# Schema.net
KiCad netlist of a schematic drawn in Altium Designer
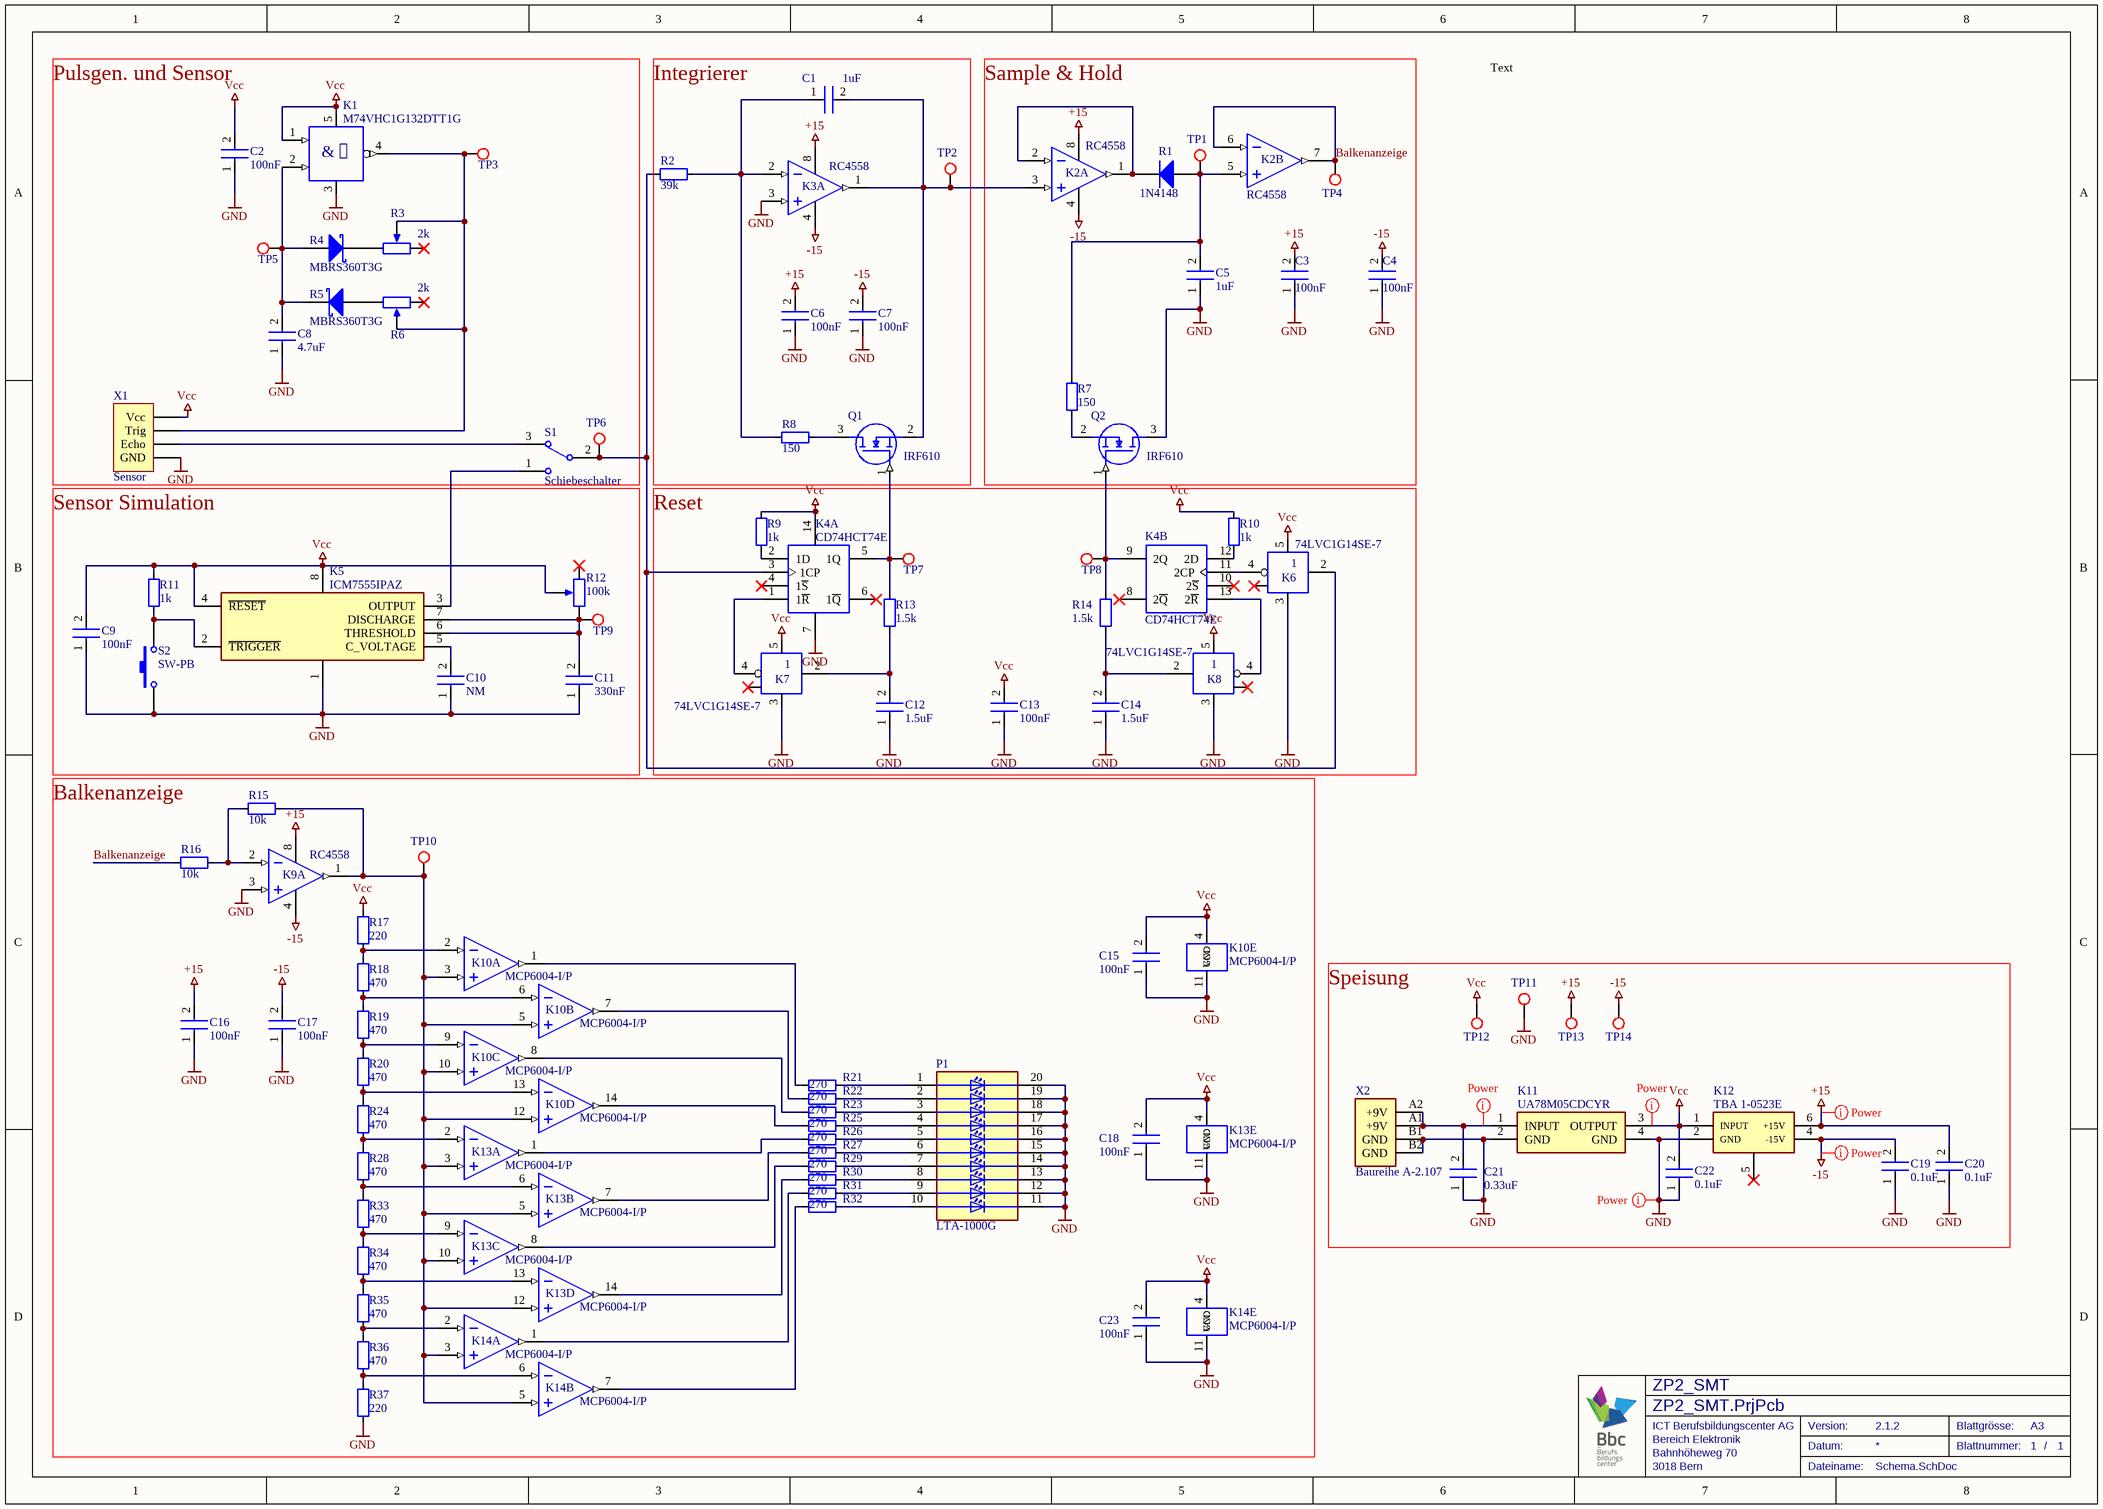
[diagram p0: Schema.SchDoc]

(export (version "E")
  (design (tool "Eeschema 10.0.6"))
  (components
    (comp (ref "C1")
      (value "1uF")
      (footprint "Footprints:okCAP CER 1206 H")
      (description "Capacitor")
      (fields
        (field (name "MANUFACTURER_PART_NUMBER") "08055A101JAT2A")
        (field (name "MOUSER PART NUMBER") "581-08055A101J")
      )
      (libsource (lib "SchemaLibrary") (part "CAP0805"))
    )
    (comp (ref "C2")
      (value "100nF")
      (footprint "Footprints:okCAP CER 1206 H")
      (description "Capacitor")
      (fields
        (field (name "MANUFACTURER_PART_NUMBER") "08055A101JAT2A")
        (field (name "MOUSER PART NUMBER") "581-08055A101J")
      )
      (libsource (lib "SchemaLibrary") (part "CAP0805"))
    )
    (comp (ref "C3")
      (value "100nF")
      (footprint "Footprints:okCAP CER 1206 H")
      (description "Capacitor")
      (fields
        (field (name "MANUFACTURER_PART_NUMBER") "08055A101JAT2A")
        (field (name "MOUSER PART NUMBER") "581-08055A101J")
      )
      (libsource (lib "SchemaLibrary") (part "CAP0805"))
    )
    (comp (ref "C4")
      (value "100nF")
      (footprint "Footprints:okCAP CER 1206 H")
      (description "Capacitor")
      (fields
        (field (name "MANUFACTURER_PART_NUMBER") "08055A101JAT2A")
        (field (name "MOUSER PART NUMBER") "581-08055A101J")
      )
      (libsource (lib "SchemaLibrary") (part "CAP0805"))
    )
    (comp (ref "C5")
      (value "1uF")
      (footprint "Footprints:okCAP CER 1206 H")
      (description "Capacitor")
      (fields
        (field (name "MANUFACTURER_PART_NUMBER") "08055A101JAT2A")
        (field (name "MOUSER PART NUMBER") "581-08055A101J")
      )
      (libsource (lib "SchemaLibrary") (part "CAP0805"))
    )
    (comp (ref "C6")
      (value "100nF")
      (footprint "Footprints:okCAP CER 1206 H")
      (description "Capacitor")
      (fields
        (field (name "MANUFACTURER_PART_NUMBER") "08055A101JAT2A")
        (field (name "MOUSER PART NUMBER") "581-08055A101J")
      )
      (libsource (lib "SchemaLibrary") (part "CAP0805"))
    )
    (comp (ref "C7")
      (value "100nF")
      (footprint "Footprints:okCAP CER 1206 H")
      (description "Capacitor")
      (fields
        (field (name "MANUFACTURER_PART_NUMBER") "08055A101JAT2A")
        (field (name "MOUSER PART NUMBER") "581-08055A101J")
      )
      (libsource (lib "SchemaLibrary") (part "CAP0805"))
    )
    (comp (ref "C8")
      (value "4.7uF")
      (footprint "Footprints:okCAP CER 1206 H")
      (description "Capacitor")
      (fields
        (field (name "MANUFACTURER_PART_NUMBER") "08055A101JAT2A")
        (field (name "MOUSER PART NUMBER") "581-08055A101J")
      )
      (libsource (lib "SchemaLibrary") (part "CAP0805"))
    )
    (comp (ref "C9")
      (value "100nF")
      (footprint "Footprints:okCAP CER 1206 H")
      (description "Capacitor")
      (fields
        (field (name "MANUFACTURER_PART_NUMBER") "08055A101JAT2A")
        (field (name "MOUSER PART NUMBER") "581-08055A101J")
      )
      (libsource (lib "SchemaLibrary") (part "CAP0805"))
    )
    (comp (ref "C10")
      (value "NM")
      (footprint "Footprints:okCAP CER 1206 H")
      (description "Capacitor")
      (fields
        (field (name "MANUFACTURER_PART_NUMBER") "08055A101JAT2A")
        (field (name "MOUSER PART NUMBER") "581-08055A101J")
      )
      (libsource (lib "SchemaLibrary") (part "CAP0805"))
    )
    (comp (ref "C11")
      (value "330nF")
      (footprint "Footprints:okCAP CER 1206 H")
      (description "Capacitor")
      (fields
        (field (name "MANUFACTURER_PART_NUMBER") "08055A101JAT2A")
        (field (name "MOUSER PART NUMBER") "581-08055A101J")
      )
      (libsource (lib "SchemaLibrary") (part "CAP0805"))
    )
    (comp (ref "C12")
      (value "1.5uF")
      (footprint "Footprints:okCAP CER 1206 H")
      (description "Capacitor")
      (fields
        (field (name "MANUFACTURER_PART_NUMBER") "08055A101JAT2A")
        (field (name "MOUSER PART NUMBER") "581-08055A101J")
      )
      (libsource (lib "SchemaLibrary") (part "CAP0805"))
    )
    (comp (ref "C13")
      (value "100nF")
      (footprint "Footprints:okCAP CER 1206 H")
      (description "Capacitor")
      (fields
        (field (name "MANUFACTURER_PART_NUMBER") "08055A101JAT2A")
        (field (name "MOUSER PART NUMBER") "581-08055A101J")
      )
      (libsource (lib "SchemaLibrary") (part "CAP0805"))
    )
    (comp (ref "C14")
      (value "1.5uF")
      (footprint "Footprints:okCAP CER 1206 H")
      (description "Capacitor")
      (fields
        (field (name "MANUFACTURER_PART_NUMBER") "08055A101JAT2A")
        (field (name "MOUSER PART NUMBER") "581-08055A101J")
      )
      (libsource (lib "SchemaLibrary") (part "CAP0805"))
    )
    (comp (ref "C15")
      (value "100nF")
      (footprint "Footprints:okCAP CER 1206 H")
      (description "Capacitor")
      (fields
        (field (name "MANUFACTURER_PART_NUMBER") "08055A101JAT2A")
        (field (name "MOUSER PART NUMBER") "581-08055A101J")
      )
      (libsource (lib "SchemaLibrary") (part "CAP0805"))
    )
    (comp (ref "C16")
      (value "100nF")
      (footprint "Footprints:okCAP CER 1206 H")
      (description "Capacitor")
      (fields
        (field (name "MANUFACTURER_PART_NUMBER") "08055A101JAT2A")
        (field (name "MOUSER PART NUMBER") "581-08055A101J")
      )
      (libsource (lib "SchemaLibrary") (part "CAP0805"))
    )
    (comp (ref "C17")
      (value "100nF")
      (footprint "Footprints:okCAP CER 1206 H")
      (description "Capacitor")
      (fields
        (field (name "MANUFACTURER_PART_NUMBER") "08055A101JAT2A")
        (field (name "MOUSER PART NUMBER") "581-08055A101J")
      )
      (libsource (lib "SchemaLibrary") (part "CAP0805"))
    )
    (comp (ref "C18")
      (value "100nF")
      (footprint "Footprints:okCAP CER 1206 H")
      (description "Capacitor")
      (fields
        (field (name "MANUFACTURER_PART_NUMBER") "08055A101JAT2A")
        (field (name "MOUSER PART NUMBER") "581-08055A101J")
      )
      (libsource (lib "SchemaLibrary") (part "CAP0805"))
    )
    (comp (ref "C19")
      (value "0.1uF")
      (footprint "Footprints:okCAP CER 1206 H")
      (description "Capacitor")
      (fields
        (field (name "MANUFACTURER_PART_NUMBER") "08055A101JAT2A")
        (field (name "MOUSER PART NUMBER") "581-08055A101J")
      )
      (libsource (lib "SchemaLibrary") (part "CAP0805"))
    )
    (comp (ref "C20")
      (value "0.1uF")
      (footprint "Footprints:okCAP CER 1206 H")
      (description "Capacitor")
      (fields
        (field (name "MANUFACTURER_PART_NUMBER") "08055A101JAT2A")
        (field (name "MOUSER PART NUMBER") "581-08055A101J")
      )
      (libsource (lib "SchemaLibrary") (part "CAP0805"))
    )
    (comp (ref "C21")
      (value "0.33uF")
      (footprint "Footprints:okCAP CER 1206 H")
      (description "Capacitor")
      (fields
        (field (name "MANUFACTURER_PART_NUMBER") "08055A101JAT2A")
        (field (name "MOUSER PART NUMBER") "581-08055A101J")
      )
      (libsource (lib "SchemaLibrary") (part "CAP0805"))
    )
    (comp (ref "C22")
      (value "0.1uF")
      (footprint "Footprints:okCAP CER 1206 H")
      (description "Capacitor")
      (fields
        (field (name "MANUFACTURER_PART_NUMBER") "08055A101JAT2A")
        (field (name "MOUSER PART NUMBER") "581-08055A101J")
      )
      (libsource (lib "SchemaLibrary") (part "CAP0805"))
    )
    (comp (ref "C23")
      (value "100nF")
      (footprint "Footprints:okCAP CER 1206 H")
      (description "Capacitor")
      (fields
        (field (name "MANUFACTURER_PART_NUMBER") "08055A101JAT2A")
        (field (name "MOUSER PART NUMBER") "581-08055A101J")
      )
      (libsource (lib "SchemaLibrary") (part "CAP0805"))
    )
    (comp (ref "K1")
      (value "M74VHC1G132DTT1G")
      (footprint "okTSOP-5")
      (description "Integrated Circuit")
      (fields
        (field (name "MANUFACTURER_PART_NUMBER") "M74VHC1G132DFT1G")
        (field (name "MOUSER PART NUMBER") "863-M74VHC1G132DFT1G")
      )
      (libsource (lib "SchemaLibrary") (part "M74VHC1G132DFT1G"))
    )
    (comp (ref "K2")
      (value "RC4558")
      (footprint "okDIP8-300")
      (description "Dual OPAMP / Dual Supply 5-15V")
      (libsource (lib "SchemaLibrary") (part "RC4558"))
    )
    (comp (ref "K3")
      (value "RC4558")
      (footprint "okDIP8-300")
      (description "Dual OPAMP / Dual Supply 5-15V")
      (libsource (lib "SchemaLibrary") (part "RC4558"))
    )
    (comp (ref "K4")
      (value "CD74HCT74E")
      (footprint "Footprints:okDIP14-300")
      (description "Integrated Circuit")
      (fields (field (name "MOUSER PART NUMBER") "595-CD74HCT74E"))
      (libsource (lib "SchemaLibrary") (part "CD74HCT74E"))
    )
    (comp (ref "K5")
      (value "ICM7555IPAZ")
      (footprint "Footprints:okDIP8-300")
      (description "Integrated Circuit")
      (fields
        (field (name "MANUFACTURER_PART_NUMBER") "ICM7555CBAZ")
        (field (name "MOUSER PART NUMBER") "968-ICM7555CBAZ")
      )
      (libsource (lib "SchemaLibrary") (part "ICM7555IPAZ"))
    )
    (comp (ref "K6")
      (value "74LVC1G14SE-7")
      (footprint "okSOT23-5")
      (description "Integrated Circuit")
      (fields
        (field (name "MANUFACTURER_PART_NUMBER") "74AHC1G04SE-7")
        (field (name "MOUSER PART NUMBER") "621-74AHC1G04SE-7")
      )
      (libsource (lib "SchemaLibrary") (part "74LVC1G14SE-7"))
    )
    (comp (ref "K7")
      (value "74LVC1G14SE-7")
      (footprint "okSOT23-5")
      (description "Integrated Circuit")
      (fields
        (field (name "MANUFACTURER_PART_NUMBER") "74AHC1G04SE-7")
        (field (name "MOUSER PART NUMBER") "621-74AHC1G04SE-7")
      )
      (libsource (lib "SchemaLibrary") (part "74LVC1G14SE-7"))
    )
    (comp (ref "K8")
      (value "74LVC1G14SE-7")
      (footprint "okSOT23-5")
      (description "Integrated Circuit")
      (fields
        (field (name "MANUFACTURER_PART_NUMBER") "74AHC1G04SE-7")
        (field (name "MOUSER PART NUMBER") "621-74AHC1G04SE-7")
      )
      (libsource (lib "SchemaLibrary") (part "74LVC1G14SE-7"))
    )
    (comp (ref "K9")
      (value "RC4558")
      (footprint "okDIP8-300")
      (description "Dual OPAMP / Dual Supply 5-15V")
      (libsource (lib "SchemaLibrary") (part "RC4558"))
    )
    (comp (ref "K10")
      (value "MCP6004-I/P")
      (footprint "okDIP14-300")
      (description "Quad OPAMP / Single Supply 1.8-6.3V / Rail to Rail")
      (libsource (lib "SchemaLibrary") (part "MCP6004-I/P"))
    )
    (comp (ref "K11")
      (value "UA78M05CDCYR")
      (footprint "okSOT23-UA78M05")
      (description "Integrated Circuit")
      (fields (field (name "MOUSER PART NUMBER") "595-UA78M05CDCYR"))
      (libsource (lib "SchemaLibrary") (part "UA78M05CDCYR"))
    )
    (comp (ref "K12")
      (value "TBA 1-0523E")
      (footprint "okTBA 1-0523E")
      (description "DC/DC")
      (libsource (lib "SchemaLibrary") (part "TBA 1-0523E"))
    )
    (comp (ref "K13")
      (value "MCP6004-I/P")
      (footprint "okDIP14-300")
      (description "Quad OPAMP / Single Supply 1.8-6.3V / Rail to Rail")
      (libsource (lib "SchemaLibrary") (part "MCP6004-I/P"))
    )
    (comp (ref "K14")
      (value "MCP6004-I/P")
      (footprint "okDIP14-300")
      (description "Quad OPAMP / Single Supply 1.8-6.3V / Rail to Rail")
      (libsource (lib "SchemaLibrary") (part "MCP6004-I/P"))
    )
    (comp (ref "P1")
      (value "LTA-1000G")
      (footprint "Footprints:okDIP20")
      (description "Display")
      (fields (field (name "MOUSER PART NUMBER") "859-LTA-1000G"))
      (libsource (lib "SchemaLibrary") (part "LTA-1000G"))
    )
    (comp (ref "Q1")
      (value "IRF610")
      (footprint "Footprints:okTO-220-1")
      (description "MOSFET (N-Channel); Reset")
      (fields (field (name "MANUFACTURER_PART_NUMBER") "2N7002"))
      (libsource (lib "SchemaLibrary") (part "IRF610"))
    )
    (comp (ref "Q2")
      (value "IRF610")
      (footprint "Footprints:okTO-220-1")
      (description "MOSFET (N-Channel); Reset")
      (fields (field (name "MANUFACTURER_PART_NUMBER") "2N7002"))
      (libsource (lib "SchemaLibrary") (part "IRF610"))
    )
    (comp (ref "R1")
      (value "1N4148")
      (footprint "okDiode 10mm")
      (description "Diode")
      (fields (field (name "PUBLISHER") "ICT Berufsbildungscenter AG"))
      (libsource (lib "SchemaLibrary") (part "Diode"))
    )
    (comp (ref "R2")
      (value "39k")
      (footprint "okRES 10mm")
      (description "Resistor")
      (fields (field (name "PUBLISHER") "ICT Berufsbildungscenter AG"))
      (libsource (lib "") (part "Resistor_1"))
    )
    (comp (ref "R3")
      (value "2k")
      (footprint "ok3362P")
      (description "Potentiometer")
      (fields (field (name "Comment") "RPot") (field (name "PUBLISHER") "Altium Limited"))
      (libsource (lib "") (part "RPot_1"))
    )
    (comp (ref "R4")
      (value "MBRS360T3G")
      (footprint "okDiode DO-214AA SMB H")
      (description "Schottky Diode")
      (fields (field (name "PUBLISHER") "Altium Limited"))
      (libsource (lib "SchemaLibrary") (part "Schottky Diode"))
    )
    (comp (ref "R5")
      (value "MBRS360T3G")
      (footprint "okDiode DO-214AA SMB H")
      (description "Schottky Diode")
      (fields (field (name "PUBLISHER") "Altium Limited"))
      (libsource (lib "SchemaLibrary") (part "Schottky Diode"))
    )
    (comp (ref "R6")
      (value "2k")
      (footprint "ok3362P")
      (description "Potentiometer")
      (fields (field (name "Comment") "RPot") (field (name "PUBLISHER") "Altium Limited"))
      (libsource (lib "SchemaLibrary") (part "RPot"))
    )
    (comp (ref "R7")
      (value "150")
      (footprint "okRES 10mm")
      (description "Resistor")
      (fields (field (name "PUBLISHER") "ICT Berufsbildungscenter AG"))
      (libsource (lib "SchemaLibrary") (part "Resistor"))
    )
    (comp (ref "R8")
      (value "150")
      (footprint "okRES 10mm")
      (description "Resistor")
      (fields (field (name "PUBLISHER") "ICT Berufsbildungscenter AG"))
      (libsource (lib "") (part "Resistor_1"))
    )
    (comp (ref "R9")
      (value "1k")
      (footprint "okRES 10mm")
      (description "Resistor")
      (fields (field (name "PUBLISHER") "ICT Berufsbildungscenter AG"))
      (libsource (lib "SchemaLibrary") (part "Resistor"))
    )
    (comp (ref "R10")
      (value "1k")
      (footprint "okRES 10mm")
      (description "Resistor")
      (fields (field (name "PUBLISHER") "ICT Berufsbildungscenter AG"))
      (libsource (lib "SchemaLibrary") (part "Resistor"))
    )
    (comp (ref "R11")
      (value "1k")
      (footprint "okRES 10mm")
      (description "Resistor")
      (fields (field (name "PUBLISHER") "ICT Berufsbildungscenter AG"))
      (libsource (lib "SchemaLibrary") (part "Resistor"))
    )
    (comp (ref "R12")
      (value "100k")
      (footprint "ok3386F")
      (description "Potentiometer")
      (fields (field (name "Comment") "RPot") (field (name "PUBLISHER") "Altium Limited"))
      (libsource (lib "SchemaLibrary") (part "RPot"))
    )
    (comp (ref "R13")
      (value "1.5k")
      (footprint "okRES 10mm")
      (description "Resistor")
      (fields (field (name "PUBLISHER") "ICT Berufsbildungscenter AG"))
      (libsource (lib "SchemaLibrary") (part "Resistor"))
    )
    (comp (ref "R14")
      (value "1.5k")
      (footprint "okRES 10mm")
      (description "Resistor")
      (fields (field (name "PUBLISHER") "ICT Berufsbildungscenter AG"))
      (libsource (lib "") (part "Resistor_2"))
    )
    (comp (ref "R15")
      (value "10k")
      (footprint "okRES 10mm")
      (description "Resistor")
      (fields (field (name "PUBLISHER") "ICT Berufsbildungscenter AG"))
      (libsource (lib "") (part "Resistor_1"))
    )
    (comp (ref "R16")
      (value "10k")
      (footprint "okRES 10mm")
      (description "Resistor")
      (fields (field (name "PUBLISHER") "ICT Berufsbildungscenter AG"))
      (libsource (lib "") (part "Resistor_1"))
    )
    (comp (ref "R17")
      (value "220")
      (footprint "okRES 10mm")
      (description "Resistor")
      (fields (field (name "PUBLISHER") "ICT Berufsbildungscenter AG"))
      (libsource (lib "SchemaLibrary") (part "Resistor"))
    )
    (comp (ref "R18")
      (value "470")
      (footprint "okRES 10mm")
      (description "Resistor")
      (fields (field (name "PUBLISHER") "ICT Berufsbildungscenter AG"))
      (libsource (lib "SchemaLibrary") (part "Resistor"))
    )
    (comp (ref "R19")
      (value "470")
      (footprint "okRES 10mm")
      (description "Resistor")
      (fields (field (name "PUBLISHER") "ICT Berufsbildungscenter AG"))
      (libsource (lib "SchemaLibrary") (part "Resistor"))
    )
    (comp (ref "R20")
      (value "470")
      (footprint "okRES 10mm")
      (description "Resistor")
      (fields (field (name "PUBLISHER") "ICT Berufsbildungscenter AG"))
      (libsource (lib "SchemaLibrary") (part "Resistor"))
    )
    (comp (ref "R21")
      (value "270")
      (footprint "okRES 10mm")
      (description "Resistor")
      (fields (field (name "PUBLISHER") "ICT Berufsbildungscenter AG"))
      (libsource (lib "") (part "Resistor_1"))
    )
    (comp (ref "R22")
      (value "270")
      (footprint "okRES 10mm")
      (description "Resistor")
      (fields (field (name "PUBLISHER") "ICT Berufsbildungscenter AG"))
      (libsource (lib "") (part "Resistor_1"))
    )
    (comp (ref "R23")
      (value "270")
      (footprint "okRES 10mm")
      (description "Resistor")
      (fields (field (name "PUBLISHER") "ICT Berufsbildungscenter AG"))
      (libsource (lib "") (part "Resistor_1"))
    )
    (comp (ref "R24")
      (value "470")
      (footprint "okRES 10mm")
      (description "Resistor")
      (fields (field (name "PUBLISHER") "ICT Berufsbildungscenter AG"))
      (libsource (lib "SchemaLibrary") (part "Resistor"))
    )
    (comp (ref "R25")
      (value "270")
      (footprint "okRES 10mm")
      (description "Resistor")
      (fields (field (name "PUBLISHER") "ICT Berufsbildungscenter AG"))
      (libsource (lib "") (part "Resistor_1"))
    )
    (comp (ref "R26")
      (value "270")
      (footprint "okRES 10mm")
      (description "Resistor")
      (fields (field (name "PUBLISHER") "ICT Berufsbildungscenter AG"))
      (libsource (lib "") (part "Resistor_1"))
    )
    (comp (ref "R27")
      (value "270")
      (footprint "okRES 10mm")
      (description "Resistor")
      (fields (field (name "PUBLISHER") "ICT Berufsbildungscenter AG"))
      (libsource (lib "") (part "Resistor_1"))
    )
    (comp (ref "R28")
      (value "470")
      (footprint "okRES 10mm")
      (description "Resistor")
      (fields (field (name "PUBLISHER") "ICT Berufsbildungscenter AG"))
      (libsource (lib "SchemaLibrary") (part "Resistor"))
    )
    (comp (ref "R29")
      (value "270")
      (footprint "okRES 10mm")
      (description "Resistor")
      (fields (field (name "PUBLISHER") "ICT Berufsbildungscenter AG"))
      (libsource (lib "") (part "Resistor_1"))
    )
    (comp (ref "R30")
      (value "270")
      (footprint "okRES 10mm")
      (description "Resistor")
      (fields (field (name "PUBLISHER") "ICT Berufsbildungscenter AG"))
      (libsource (lib "") (part "Resistor_1"))
    )
    (comp (ref "R31")
      (value "270")
      (footprint "okRES 10mm")
      (description "Resistor")
      (fields (field (name "PUBLISHER") "ICT Berufsbildungscenter AG"))
      (libsource (lib "") (part "Resistor_1"))
    )
    (comp (ref "R32")
      (value "270")
      (footprint "okRES 10mm")
      (description "Resistor")
      (fields (field (name "PUBLISHER") "ICT Berufsbildungscenter AG"))
      (libsource (lib "") (part "Resistor_1"))
    )
    (comp (ref "R33")
      (value "470")
      (footprint "okRES 10mm")
      (description "Resistor")
      (fields (field (name "PUBLISHER") "ICT Berufsbildungscenter AG"))
      (libsource (lib "SchemaLibrary") (part "Resistor"))
    )
    (comp (ref "R34")
      (value "470")
      (footprint "okRES 10mm")
      (description "Resistor")
      (fields (field (name "PUBLISHER") "ICT Berufsbildungscenter AG"))
      (libsource (lib "SchemaLibrary") (part "Resistor"))
    )
    (comp (ref "R35")
      (value "470")
      (footprint "okRES 10mm")
      (description "Resistor")
      (fields (field (name "PUBLISHER") "ICT Berufsbildungscenter AG"))
      (libsource (lib "SchemaLibrary") (part "Resistor"))
    )
    (comp (ref "R36")
      (value "470")
      (footprint "okRES 10mm")
      (description "Resistor")
      (fields (field (name "PUBLISHER") "ICT Berufsbildungscenter AG"))
      (libsource (lib "SchemaLibrary") (part "Resistor"))
    )
    (comp (ref "R37")
      (value "220")
      (footprint "okRES 10mm")
      (description "Resistor")
      (fields (field (name "PUBLISHER") "ICT Berufsbildungscenter AG"))
      (libsource (lib "SchemaLibrary") (part "Resistor"))
    )
    (comp (ref "S1")
      (value "Schiebeschalter")
      (footprint "okSCHIEBESCHALTER")
      (description "Switch, THT")
      (fields (field (name "PUBLISHER") "Altium Limited"))
      (libsource (lib "SchemaLibrary") (part "Schiebeschalter"))
    )
    (comp (ref "S2")
      (value "SW-PB")
      (footprint "okdrucktaster")
      (description "Switch, SMD")
      (fields (field (name "PUBLISHER") "Altium Limited"))
      (libsource (lib "SchemaLibrary") (part "Drucktaster"))
    )
    (comp (ref "TP1")
      (value "Lötstützpunkt")
      (footprint "okLötstützpunkt")
      (libsource (lib "SchemaLibrary") (part "Testpunkt"))
    )
    (comp (ref "TP2")
      (value "Lötstützpunkt")
      (footprint "okLötstützpunkt")
      (libsource (lib "SchemaLibrary") (part "Testpunkt"))
    )
    (comp (ref "TP3")
      (value "Lötstützpunkt")
      (footprint "okLötstützpunkt")
      (libsource (lib "SchemaLibrary") (part "Testpunkt"))
    )
    (comp (ref "TP4")
      (value "Lötstützpunkt")
      (footprint "okLötstützpunkt")
      (libsource (lib "SchemaLibrary") (part "Testpunkt"))
    )
    (comp (ref "TP5")
      (value "Lötstützpunkt")
      (footprint "okLötstützpunkt")
      (libsource (lib "SchemaLibrary") (part "Testpunkt"))
    )
    (comp (ref "TP6")
      (value "Lötstützpunkt")
      (footprint "okLötstützpunkt")
      (libsource (lib "SchemaLibrary") (part "Testpunkt"))
    )
    (comp (ref "TP7")
      (value "Lötstützpunkt")
      (footprint "okLötstützpunkt")
      (libsource (lib "SchemaLibrary") (part "Testpunkt"))
    )
    (comp (ref "TP8")
      (value "Lötstützpunkt")
      (footprint "okLötstützpunkt")
      (libsource (lib "SchemaLibrary") (part "Testpunkt"))
    )
    (comp (ref "TP9")
      (value "Lötstützpunkt")
      (footprint "okLötstützpunkt")
      (libsource (lib "SchemaLibrary") (part "Testpunkt"))
    )
    (comp (ref "TP10")
      (value "Lötstützpunkt")
      (footprint "okLötstützpunkt")
      (libsource (lib "SchemaLibrary") (part "Testpunkt"))
    )
    (comp (ref "TP11")
      (value "Lötstützpunkt")
      (footprint "okLötstützpunkt")
      (libsource (lib "SchemaLibrary") (part "Testpunkt"))
    )
    (comp (ref "TP12")
      (value "Lötstützpunkt")
      (footprint "okLötstützpunkt")
      (libsource (lib "SchemaLibrary") (part "Testpunkt"))
    )
    (comp (ref "TP13")
      (value "Lötstützpunkt")
      (footprint "okLötstützpunkt")
      (libsource (lib "SchemaLibrary") (part "Testpunkt"))
    )
    (comp (ref "TP14")
      (value "Lötstützpunkt")
      (footprint "okLötstützpunkt")
      (libsource (lib "SchemaLibrary") (part "Testpunkt"))
    )
    (comp (ref "X1")
      (value "Sensor")
      (footprint "okHeader Female 4pin")
      (description "Header, 4-Pin")
      (fields (field (name "PUBLISHER") "Altium Limited"))
      (libsource (lib "SchemaLibrary") (part "Header 4"))
    )
    (comp (ref "X2")
      (value "Baureihe A-2.107")
      (footprint "ok24.243.X")
      (description "Laborgerätanschluss, 4mm")
      (fields (field (name "PUBLISHER") "Altium Limited"))
      (libsource (lib "SchemaLibrary") (part "Bananenstecker"))
    )
  )
  (nets
    (net (code "1") (name "+15") (class "Default")
      (node (ref "C16") (pin "2") (pinfunction "2_2") (pintype "passive"))
      (node (ref "C20") (pin "2") (pinfunction "2_2") (pintype "passive"))
      (node (ref "C3") (pin "2") (pinfunction "2_2") (pintype "passive"))
      (node (ref "C6") (pin "2") (pinfunction "2_2") (pintype "passive"))
      (node (ref "K12") (pin "6") (pinfunction "+15V_6") (pintype "passive"))
      (node (ref "K2") (pin "8") (pinfunction "V+_8") (pintype "power_in"))
      (node (ref "K3") (pin "8") (pinfunction "V+_8") (pintype "power_in"))
      (node (ref "K9") (pin "8") (pinfunction "V+_8") (pintype "power_in"))
      (node (ref "TP13") (pin "1") (pinfunction "1_1") (pintype "passive"))
    )
    (net (code "2") (name "-15") (class "Default")
      (node (ref "C17") (pin "2") (pinfunction "2_2") (pintype "passive"))
      (node (ref "C19") (pin "2") (pinfunction "2_2") (pintype "passive"))
      (node (ref "C4") (pin "2") (pinfunction "2_2") (pintype "passive"))
      (node (ref "C7") (pin "2") (pinfunction "2_2") (pintype "passive"))
      (node (ref "K12") (pin "4") (pinfunction "-15V_4") (pintype "passive"))
      (node (ref "K2") (pin "4") (pinfunction "V-_4") (pintype "power_in"))
      (node (ref "K3") (pin "4") (pinfunction "V-_4") (pintype "power_in"))
      (node (ref "K9") (pin "4") (pinfunction "V-_4") (pintype "power_in"))
      (node (ref "TP14") (pin "1") (pinfunction "1_1") (pintype "passive"))
    )
    (net (code "3") (name "/Balkenanzeige") (class "Default")
      (node (ref "K2") (pin "6") (pinfunction "IN2-_6") (pintype "input"))
      (node (ref "K2") (pin "7") (pinfunction "OUT2_7") (pintype "output"))
      (node (ref "R16") (pin "1") (pinfunction "1_1") (pintype "passive"))
      (node (ref "TP4") (pin "1") (pinfunction "1_1") (pintype "passive"))
    )
    (net (code "4") (name "GND") (class "Default")
      (node (ref "C10") (pin "1") (pinfunction "1_1") (pintype "passive"))
      (node (ref "C11") (pin "1") (pinfunction "1_1") (pintype "passive"))
      (node (ref "C12") (pin "1") (pinfunction "1_1") (pintype "passive"))
      (node (ref "C13") (pin "1") (pinfunction "1_1") (pintype "passive"))
      (node (ref "C14") (pin "1") (pinfunction "1_1") (pintype "passive"))
      (node (ref "C15") (pin "1") (pinfunction "1_1") (pintype "passive"))
      (node (ref "C16") (pin "1") (pinfunction "1_1") (pintype "passive"))
      (node (ref "C17") (pin "1") (pinfunction "1_1") (pintype "passive"))
      (node (ref "C18") (pin "1") (pinfunction "1_1") (pintype "passive"))
      (node (ref "C19") (pin "1") (pinfunction "1_1") (pintype "passive"))
      (node (ref "C2") (pin "1") (pinfunction "1_1") (pintype "passive"))
      (node (ref "C20") (pin "1") (pinfunction "1_1") (pintype "passive"))
      (node (ref "C21") (pin "1") (pinfunction "1_1") (pintype "passive"))
      (node (ref "C22") (pin "1") (pinfunction "1_1") (pintype "passive"))
      (node (ref "C23") (pin "1") (pinfunction "1_1") (pintype "passive"))
      (node (ref "C3") (pin "1") (pinfunction "1_1") (pintype "passive"))
      (node (ref "C4") (pin "1") (pinfunction "1_1") (pintype "passive"))
      (node (ref "C5") (pin "1") (pinfunction "1_1") (pintype "passive"))
      (node (ref "C6") (pin "1") (pinfunction "1_1") (pintype "passive"))
      (node (ref "C7") (pin "1") (pinfunction "1_1") (pintype "passive"))
      (node (ref "C8") (pin "1") (pinfunction "1_1") (pintype "passive"))
      (node (ref "C9") (pin "1") (pinfunction "1_1") (pintype "passive"))
      (node (ref "K1") (pin "3") (pinfunction "GND_3") (pintype "power_in"))
      (node (ref "K10") (pin "11") (pinfunction "GND_11") (pintype "power_in"))
      (node (ref "K11") (pin "2") (pinfunction "GND_2") (pintype "passive"))
      (node (ref "K11") (pin "4") (pinfunction "GND_4") (pintype "passive"))
      (node (ref "K12") (pin "2") (pinfunction "GND_2") (pintype "passive"))
      (node (ref "K13") (pin "11") (pinfunction "GND_11") (pintype "power_in"))
      (node (ref "K14") (pin "11") (pinfunction "GND_11") (pintype "power_in"))
      (node (ref "K3") (pin "3") (pinfunction "IN1+_3") (pintype "input"))
      (node (ref "K4") (pin "7") (pinfunction "GND_7") (pintype "passive"))
      (node (ref "K5") (pin "1") (pinfunction "GND_1") (pintype "passive"))
      (node (ref "K6") (pin "3") (pinfunction "GND_3") (pintype "passive"))
      (node (ref "K7") (pin "3") (pinfunction "GND_3") (pintype "passive"))
      (node (ref "K8") (pin "3") (pinfunction "GND_3") (pintype "passive"))
      (node (ref "K9") (pin "3") (pinfunction "IN1+_3") (pintype "input"))
      (node (ref "P1") (pin "11") (pinfunction "CATHODE_K_11") (pintype "passive"))
      (node (ref "P1") (pin "12") (pinfunction "CATHODE_J_12") (pintype "passive"))
      (node (ref "P1") (pin "13") (pinfunction "CATHODE_H_13") (pintype "passive"))
      (node (ref "P1") (pin "14") (pinfunction "CATHODE_G_14") (pintype "passive"))
      (node (ref "P1") (pin "15") (pinfunction "CATHODE_F_15") (pintype "passive"))
      (node (ref "P1") (pin "16") (pinfunction "CATHODE_E_16") (pintype "passive"))
      (node (ref "P1") (pin "17") (pinfunction "CATHODE_D_17") (pintype "passive"))
      (node (ref "P1") (pin "18") (pinfunction "CATHODE_C_18") (pintype "passive"))
      (node (ref "P1") (pin "19") (pinfunction "CATHODE_B_19") (pintype "passive"))
      (node (ref "P1") (pin "20") (pinfunction "CATHODE_A_20") (pintype "passive"))
      (node (ref "Q2") (pin "3") (pinfunction "D_3") (pintype "passive"))
      (node (ref "R37") (pin "1") (pinfunction "1_1") (pintype "passive"))
      (node (ref "S2") (pin "4") (pinfunction "4_4") (pintype "passive"))
      (node (ref "TP11") (pin "1") (pinfunction "1_1") (pintype "passive"))
      (node (ref "X1") (pin "4") (pinfunction "GND_4") (pintype "passive"))
      (node (ref "X2") (pin "B1") (pinfunction "GND_B1") (pintype "passive"))
      (node (ref "X2") (pin "B2") (pinfunction "GND_B2") (pintype "passive"))
    )
    (net (code "5") (name "Net-(K1-B)") (class "Default")
      (node (ref "C8") (pin "2") (pinfunction "2_2") (pintype "passive"))
      (node (ref "K1") (pin "2") (pinfunction "B_2") (pintype "input"))
      (node (ref "R4") (pin "3") (pinfunction "A_3") (pintype "passive"))
      (node (ref "R5") (pin "1") (pinfunction "K_1") (pintype "passive"))
      (node (ref "TP5") (pin "1") (pinfunction "1_1") (pintype "passive"))
    )
    (net (code "6") (name "Net-(K1-~{Y})") (class "Default")
      (node (ref "K1") (pin "4") (pinfunction "~{Y}_4") (pintype "output"))
      (node (ref "R3") (pin "2") (pinfunction "TAP_2") (pintype "passive"))
      (node (ref "R6") (pin "2") (pinfunction "TAP_2") (pintype "passive"))
      (node (ref "TP3") (pin "1") (pinfunction "1_1") (pintype "passive"))
      (node (ref "X1") (pin "2") (pinfunction "Trig_2") (pintype "passive"))
    )
    (net (code "7") (name "Net-(K2A-IN1+)") (class "Default")
      (node (ref "C1") (pin "2") (pinfunction "2_2") (pintype "passive"))
      (node (ref "K2") (pin "3") (pinfunction "IN1+_3") (pintype "input"))
      (node (ref "K3") (pin "1") (pinfunction "OUT1_1") (pintype "output"))
      (node (ref "Q1") (pin "2") (pinfunction "S_2") (pintype "passive"))
      (node (ref "TP2") (pin "1") (pinfunction "1_1") (pintype "passive"))
    )
    (net (code "8") (name "Net-(K2A-IN1-)") (class "Default")
      (node (ref "K2") (pin "1") (pinfunction "OUT1_1") (pintype "output"))
      (node (ref "K2") (pin "2") (pinfunction "IN1-_2") (pintype "input"))
      (node (ref "R1") (pin "C") (pinfunction "Cathode_C") (pintype "passive"))
    )
    (net (code "9") (name "Net-(K2B-IN2+)") (class "Default")
      (node (ref "C5") (pin "2") (pinfunction "2_2") (pintype "passive"))
      (node (ref "K2") (pin "5") (pinfunction "IN2+_5") (pintype "input"))
      (node (ref "R1") (pin "A") (pinfunction "Anode_A") (pintype "passive"))
      (node (ref "R7") (pin "2") (pinfunction "2_2") (pintype "passive"))
      (node (ref "TP1") (pin "1") (pinfunction "1_1") (pintype "passive"))
    )
    (net (code "10") (name "Net-(K3A-IN1-)") (class "Default")
      (node (ref "C1") (pin "1") (pinfunction "1_1") (pintype "passive"))
      (node (ref "K3") (pin "2") (pinfunction "IN1-_2") (pintype "input"))
      (node (ref "R2") (pin "2") (pinfunction "2_2") (pintype "passive"))
      (node (ref "R8") (pin "1") (pinfunction "1_1") (pintype "passive"))
    )
    (net (code "11") (name "Net-(K4A-1CP)") (class "Default")
      (node (ref "K4") (pin "3") (pinfunction "1CP_3") (pintype "passive"))
      (node (ref "K6") (pin "2") (pinfunction "A_2") (pintype "passive"))
      (node (ref "R2") (pin "1") (pinfunction "1_1") (pintype "passive"))
      (node (ref "S1") (pin "2") (pinfunction "2_2") (pintype "passive"))
      (node (ref "TP6") (pin "1") (pinfunction "1_1") (pintype "passive"))
    )
    (net (code "12") (name "Net-(K4A-1D)") (class "Default")
      (node (ref "K4") (pin "2") (pinfunction "1D_2") (pintype "passive"))
      (node (ref "R9") (pin "1") (pinfunction "1_1") (pintype "passive"))
    )
    (net (code "13") (name "Net-(K4A-1Q)") (class "Default")
      (node (ref "K4") (pin "5") (pinfunction "1Q_5") (pintype "passive"))
      (node (ref "Q1") (pin "1") (pinfunction "G_1") (pintype "input"))
      (node (ref "R13") (pin "2") (pinfunction "2_2") (pintype "passive"))
      (node (ref "TP7") (pin "1") (pinfunction "1_1") (pintype "passive"))
    )
    (net (code "14") (name "Net-(K4A-1~{R})") (class "Default")
      (node (ref "K4") (pin "1") (pinfunction "1~{R}_1") (pintype "passive"))
      (node (ref "K7") (pin "4") (pinfunction "Y_4") (pintype "passive"))
    )
    (net (code "15") (name "Net-(K4B-2CP)") (class "Default")
      (node (ref "K4") (pin "11") (pinfunction "2CP_11") (pintype "passive"))
      (node (ref "K6") (pin "4") (pinfunction "Y_4") (pintype "passive"))
    )
    (net (code "16") (name "Net-(K4B-2D)") (class "Default")
      (node (ref "K4") (pin "12") (pinfunction "2D_12") (pintype "passive"))
      (node (ref "R10") (pin "1") (pinfunction "1_1") (pintype "passive"))
    )
    (net (code "17") (name "Net-(K4B-2Q)") (class "Default")
      (node (ref "K4") (pin "9") (pinfunction "2Q_9") (pintype "passive"))
      (node (ref "Q2") (pin "1") (pinfunction "G_1") (pintype "input"))
      (node (ref "R14") (pin "1") (pinfunction "1_1") (pintype "passive"))
      (node (ref "TP8") (pin "1") (pinfunction "1_1") (pintype "passive"))
    )
    (net (code "18") (name "Net-(K4B-2~{R})") (class "Default")
      (node (ref "K4") (pin "13") (pinfunction "2~{R}_13") (pintype "passive"))
      (node (ref "K8") (pin "4") (pinfunction "Y_4") (pintype "passive"))
    )
    (net (code "19") (name "Net-(K5-C_VOLTAGE)") (class "Default")
      (node (ref "C10") (pin "2") (pinfunction "2_2") (pintype "passive"))
      (node (ref "K5") (pin "5") (pinfunction "C_VOLTAGE_5") (pintype "passive"))
    )
    (net (code "20") (name "Net-(K5-DISCHARGE)") (class "Default")
      (node (ref "C11") (pin "2") (pinfunction "2_2") (pintype "passive"))
      (node (ref "K5") (pin "6") (pinfunction "THRESHOLD_6") (pintype "passive"))
      (node (ref "K5") (pin "7") (pinfunction "DISCHARGE_7") (pintype "passive"))
      (node (ref "R12") (pin "1") (pinfunction "BOT_1") (pintype "passive"))
      (node (ref "TP9") (pin "1") (pinfunction "1_1") (pintype "passive"))
    )
    (net (code "21") (name "Net-(K5-OUTPUT)") (class "Default")
      (node (ref "K5") (pin "3") (pinfunction "OUTPUT_3") (pintype "passive"))
      (node (ref "S1") (pin "1") (pinfunction "1_1") (pintype "passive"))
    )
    (net (code "22") (name "Net-(K5-~{TRIGGER})") (class "Default")
      (node (ref "K5") (pin "2") (pinfunction "~{TRIGGER}_2") (pintype "passive"))
      (node (ref "R11") (pin "1") (pinfunction "1_1") (pintype "passive"))
      (node (ref "S2") (pin "1") (pinfunction "1_1") (pintype "passive"))
    )
    (net (code "23") (name "Net-(K7-A)") (class "Default")
      (node (ref "C12") (pin "2") (pinfunction "2_2") (pintype "passive"))
      (node (ref "K7") (pin "2") (pinfunction "A_2") (pintype "passive"))
      (node (ref "R13") (pin "1") (pinfunction "1_1") (pintype "passive"))
    )
    (net (code "24") (name "Net-(K8-A)") (class "Default")
      (node (ref "C14") (pin "2") (pinfunction "2_2") (pintype "passive"))
      (node (ref "K8") (pin "2") (pinfunction "A_2") (pintype "passive"))
      (node (ref "R14") (pin "2") (pinfunction "2_2") (pintype "passive"))
    )
    (net (code "25") (name "Net-(K9A-IN1-)") (class "Default")
      (node (ref "K9") (pin "2") (pinfunction "IN1-_2") (pintype "input"))
      (node (ref "R15") (pin "1") (pinfunction "1_1") (pintype "passive"))
      (node (ref "R16") (pin "2") (pinfunction "2_2") (pintype "passive"))
    )
    (net (code "26") (name "Net-(K10A-VINA+)") (class "Default")
      (node (ref "K10") (pin "10") (pinfunction "VINC+_10") (pintype "input"))
      (node (ref "K10") (pin "12") (pinfunction "VIND+_12") (pintype "input"))
      (node (ref "K10") (pin "3") (pinfunction "VINA+_3") (pintype "input"))
      (node (ref "K10") (pin "5") (pinfunction "VINB+_5") (pintype "input"))
      (node (ref "K13") (pin "10") (pinfunction "VINC+_10") (pintype "input"))
      (node (ref "K13") (pin "12") (pinfunction "VIND+_12") (pintype "input"))
      (node (ref "K13") (pin "3") (pinfunction "VINA+_3") (pintype "input"))
      (node (ref "K13") (pin "5") (pinfunction "VINB+_5") (pintype "input"))
      (node (ref "K14") (pin "3") (pinfunction "VINA+_3") (pintype "input"))
      (node (ref "K14") (pin "5") (pinfunction "VINB+_5") (pintype "input"))
      (node (ref "K9") (pin "1") (pinfunction "OUT1_1") (pintype "output"))
      (node (ref "R15") (pin "2") (pinfunction "2_2") (pintype "passive"))
      (node (ref "TP10") (pin "1") (pinfunction "1_1") (pintype "passive"))
    )
    (net (code "27") (name "Net-(K10A-VINA-)") (class "Default")
      (node (ref "K10") (pin "2") (pinfunction "VINA-_2") (pintype "input"))
      (node (ref "R17") (pin "1") (pinfunction "1_1") (pintype "passive"))
      (node (ref "R18") (pin "2") (pinfunction "2_2") (pintype "passive"))
    )
    (net (code "28") (name "Net-(K10A-VOUTA)") (class "Default")
      (node (ref "K10") (pin "1") (pinfunction "VOUTA_1") (pintype "output"))
      (node (ref "R21") (pin "1") (pinfunction "1_1") (pintype "passive"))
    )
    (net (code "29") (name "Net-(K10B-VINB-)") (class "Default")
      (node (ref "K10") (pin "6") (pinfunction "VINB-_6") (pintype "input"))
      (node (ref "R18") (pin "1") (pinfunction "1_1") (pintype "passive"))
      (node (ref "R19") (pin "2") (pinfunction "2_2") (pintype "passive"))
    )
    (net (code "30") (name "Net-(K10B-VOUTB)") (class "Default")
      (node (ref "K10") (pin "7") (pinfunction "VOUTB_7") (pintype "output"))
      (node (ref "R22") (pin "1") (pinfunction "1_1") (pintype "passive"))
    )
    (net (code "31") (name "Net-(K10C-VINC-)") (class "Default")
      (node (ref "K10") (pin "9") (pinfunction "VINC-_9") (pintype "input"))
      (node (ref "R19") (pin "1") (pinfunction "1_1") (pintype "passive"))
      (node (ref "R20") (pin "2") (pinfunction "2_2") (pintype "passive"))
    )
    (net (code "32") (name "Net-(K10C-VOUTC)") (class "Default")
      (node (ref "K10") (pin "8") (pinfunction "VOUTC_8") (pintype "output"))
      (node (ref "R23") (pin "1") (pinfunction "1_1") (pintype "passive"))
    )
    (net (code "33") (name "Net-(K10D-VIND-)") (class "Default")
      (node (ref "K10") (pin "13") (pinfunction "VIND-_13") (pintype "input"))
      (node (ref "R20") (pin "1") (pinfunction "1_1") (pintype "passive"))
      (node (ref "R24") (pin "2") (pinfunction "2_2") (pintype "passive"))
    )
    (net (code "34") (name "Net-(K10D-VOUTD)") (class "Default")
      (node (ref "K10") (pin "14") (pinfunction "VOUTD_14") (pintype "output"))
      (node (ref "R25") (pin "1") (pinfunction "1_1") (pintype "passive"))
    )
    (net (code "35") (name "Net-(K11-INPUT)") (class "Default")
      (node (ref "C21") (pin "2") (pinfunction "2_2") (pintype "passive"))
      (node (ref "K11") (pin "1") (pinfunction "INPUT_1") (pintype "passive"))
      (node (ref "X2") (pin "A1") (pinfunction "+9V_A1") (pintype "passive"))
      (node (ref "X2") (pin "A2") (pinfunction "+9V_A2") (pintype "passive"))
    )
    (net (code "36") (name "Net-(K13A-VINA-)") (class "Default")
      (node (ref "K13") (pin "2") (pinfunction "VINA-_2") (pintype "input"))
      (node (ref "R24") (pin "1") (pinfunction "1_1") (pintype "passive"))
      (node (ref "R28") (pin "2") (pinfunction "2_2") (pintype "passive"))
    )
    (net (code "37") (name "Net-(K13A-VOUTA)") (class "Default")
      (node (ref "K13") (pin "1") (pinfunction "VOUTA_1") (pintype "output"))
      (node (ref "R26") (pin "1") (pinfunction "1_1") (pintype "passive"))
    )
    (net (code "38") (name "Net-(K13B-VINB-)") (class "Default")
      (node (ref "K13") (pin "6") (pinfunction "VINB-_6") (pintype "input"))
      (node (ref "R28") (pin "1") (pinfunction "1_1") (pintype "passive"))
      (node (ref "R33") (pin "2") (pinfunction "2_2") (pintype "passive"))
    )
    (net (code "39") (name "Net-(K13B-VOUTB)") (class "Default")
      (node (ref "K13") (pin "7") (pinfunction "VOUTB_7") (pintype "output"))
      (node (ref "R27") (pin "1") (pinfunction "1_1") (pintype "passive"))
    )
    (net (code "40") (name "Net-(K13C-VINC-)") (class "Default")
      (node (ref "K13") (pin "9") (pinfunction "VINC-_9") (pintype "input"))
      (node (ref "R33") (pin "1") (pinfunction "1_1") (pintype "passive"))
      (node (ref "R34") (pin "2") (pinfunction "2_2") (pintype "passive"))
    )
    (net (code "41") (name "Net-(K13C-VOUTC)") (class "Default")
      (node (ref "K13") (pin "8") (pinfunction "VOUTC_8") (pintype "output"))
      (node (ref "R29") (pin "1") (pinfunction "1_1") (pintype "passive"))
    )
    (net (code "42") (name "Net-(K13D-VIND-)") (class "Default")
      (node (ref "K13") (pin "13") (pinfunction "VIND-_13") (pintype "input"))
      (node (ref "R34") (pin "1") (pinfunction "1_1") (pintype "passive"))
      (node (ref "R35") (pin "2") (pinfunction "2_2") (pintype "passive"))
    )
    (net (code "43") (name "Net-(K13D-VOUTD)") (class "Default")
      (node (ref "K13") (pin "14") (pinfunction "VOUTD_14") (pintype "output"))
      (node (ref "R30") (pin "1") (pinfunction "1_1") (pintype "passive"))
    )
    (net (code "44") (name "Net-(K14A-VINA-)") (class "Default")
      (node (ref "K14") (pin "2") (pinfunction "VINA-_2") (pintype "input"))
      (node (ref "R35") (pin "1") (pinfunction "1_1") (pintype "passive"))
      (node (ref "R36") (pin "2") (pinfunction "2_2") (pintype "passive"))
    )
    (net (code "45") (name "Net-(K14A-VOUTA)") (class "Default")
      (node (ref "K14") (pin "1") (pinfunction "VOUTA_1") (pintype "output"))
      (node (ref "R31") (pin "1") (pinfunction "1_1") (pintype "passive"))
    )
    (net (code "46") (name "Net-(K14B-VINB-)") (class "Default")
      (node (ref "K14") (pin "6") (pinfunction "VINB-_6") (pintype "input"))
      (node (ref "R36") (pin "1") (pinfunction "1_1") (pintype "passive"))
      (node (ref "R37") (pin "2") (pinfunction "2_2") (pintype "passive"))
    )
    (net (code "47") (name "Net-(K14B-VOUTB)") (class "Default")
      (node (ref "K14") (pin "7") (pinfunction "VOUTB_7") (pintype "output"))
      (node (ref "R32") (pin "1") (pinfunction "1_1") (pintype "passive"))
    )
    (net (code "48") (name "Net-(P1-ANODE_A)") (class "Default")
      (node (ref "P1") (pin "1") (pinfunction "ANODE_A_1") (pintype "passive"))
      (node (ref "R21") (pin "2") (pinfunction "2_2") (pintype "passive"))
    )
    (net (code "49") (name "Net-(P1-ANODE_B)") (class "Default")
      (node (ref "P1") (pin "2") (pinfunction "ANODE_B_2") (pintype "passive"))
      (node (ref "R22") (pin "2") (pinfunction "2_2") (pintype "passive"))
    )
    (net (code "50") (name "Net-(P1-ANODE_C)") (class "Default")
      (node (ref "P1") (pin "3") (pinfunction "ANODE_C_3") (pintype "passive"))
      (node (ref "R23") (pin "2") (pinfunction "2_2") (pintype "passive"))
    )
    (net (code "51") (name "Net-(P1-ANODE_D)") (class "Default")
      (node (ref "P1") (pin "4") (pinfunction "ANODE_D_4") (pintype "passive"))
      (node (ref "R25") (pin "2") (pinfunction "2_2") (pintype "passive"))
    )
    (net (code "52") (name "Net-(P1-ANODE_E)") (class "Default")
      (node (ref "P1") (pin "5") (pinfunction "ANODE_E_5") (pintype "passive"))
      (node (ref "R26") (pin "2") (pinfunction "2_2") (pintype "passive"))
    )
    (net (code "53") (name "Net-(P1-ANODE_F)") (class "Default")
      (node (ref "P1") (pin "6") (pinfunction "ANODE_F_6") (pintype "passive"))
      (node (ref "R27") (pin "2") (pinfunction "2_2") (pintype "passive"))
    )
    (net (code "54") (name "Net-(P1-ANODE_G)") (class "Default")
      (node (ref "P1") (pin "7") (pinfunction "ANODE_G_7") (pintype "passive"))
      (node (ref "R29") (pin "2") (pinfunction "2_2") (pintype "passive"))
    )
    (net (code "55") (name "Net-(P1-ANODE_H)") (class "Default")
      (node (ref "P1") (pin "8") (pinfunction "ANODE_H_8") (pintype "passive"))
      (node (ref "R30") (pin "2") (pinfunction "2_2") (pintype "passive"))
    )
    (net (code "56") (name "Net-(P1-ANODE_J)") (class "Default")
      (node (ref "P1") (pin "9") (pinfunction "ANODE_J_9") (pintype "passive"))
      (node (ref "R31") (pin "2") (pinfunction "2_2") (pintype "passive"))
    )
    (net (code "57") (name "Net-(P1-ANODE__K)") (class "Default")
      (node (ref "P1") (pin "10") (pinfunction "ANODE__K_10") (pintype "passive"))
      (node (ref "R32") (pin "2") (pinfunction "2_2") (pintype "passive"))
    )
    (net (code "58") (name "Net-(Q1-D)") (class "Default")
      (node (ref "Q1") (pin "3") (pinfunction "D_3") (pintype "passive"))
      (node (ref "R8") (pin "2") (pinfunction "2_2") (pintype "passive"))
    )
    (net (code "59") (name "Net-(Q2-S)") (class "Default")
      (node (ref "Q2") (pin "2") (pinfunction "S_2") (pintype "passive"))
      (node (ref "R7") (pin "1") (pinfunction "1_1") (pintype "passive"))
    )
    (net (code "60") (name "Net-(R3-BOT)") (class "Default")
      (node (ref "R3") (pin "1") (pinfunction "BOT_1") (pintype "passive"))
      (node (ref "R4") (pin "1") (pinfunction "K_1") (pintype "passive"))
    )
    (net (code "61") (name "Net-(R5-A)") (class "Default")
      (node (ref "R5") (pin "3") (pinfunction "A_3") (pintype "passive"))
      (node (ref "R6") (pin "1") (pinfunction "BOT_1") (pintype "passive"))
    )
    (net (code "62") (name "Net-(X1-Echo)") (class "Default")
      (node (ref "S1") (pin "3") (pinfunction "3_3") (pintype "passive"))
      (node (ref "X1") (pin "3") (pinfunction "Echo_3") (pintype "passive"))
    )
    (net (code "63") (name "Vcc") (class "Default")
      (node (ref "C13") (pin "2") (pinfunction "2_2") (pintype "passive"))
      (node (ref "C15") (pin "2") (pinfunction "2_2") (pintype "passive"))
      (node (ref "C18") (pin "2") (pinfunction "2_2") (pintype "passive"))
      (node (ref "C2") (pin "2") (pinfunction "2_2") (pintype "passive"))
      (node (ref "C22") (pin "2") (pinfunction "2_2") (pintype "passive"))
      (node (ref "C23") (pin "2") (pinfunction "2_2") (pintype "passive"))
      (node (ref "C9") (pin "2") (pinfunction "2_2") (pintype "passive"))
      (node (ref "K1") (pin "1") (pinfunction "A_1") (pintype "input"))
      (node (ref "K1") (pin "5") (pinfunction "VCC_5") (pintype "power_in"))
      (node (ref "K10") (pin "4") (pinfunction "VCC_4") (pintype "power_in"))
      (node (ref "K11") (pin "3") (pinfunction "OUTPUT_3") (pintype "passive"))
      (node (ref "K12") (pin "1") (pinfunction "INPUT_1") (pintype "passive"))
      (node (ref "K13") (pin "4") (pinfunction "VCC_4") (pintype "power_in"))
      (node (ref "K14") (pin "4") (pinfunction "VCC_4") (pintype "power_in"))
      (node (ref "K4") (pin "14") (pinfunction "VCC_14") (pintype "passive"))
      (node (ref "K5") (pin "4") (pinfunction "~{RESET}_4") (pintype "passive"))
      (node (ref "K5") (pin "8") (pinfunction "VDD_8") (pintype "passive"))
      (node (ref "K6") (pin "5") (pinfunction "Vcc_5") (pintype "passive"))
      (node (ref "K7") (pin "5") (pinfunction "Vcc_5") (pintype "passive"))
      (node (ref "K8") (pin "5") (pinfunction "Vcc_5") (pintype "passive"))
      (node (ref "R10") (pin "2") (pinfunction "2_2") (pintype "passive"))
      (node (ref "R11") (pin "2") (pinfunction "2_2") (pintype "passive"))
      (node (ref "R12") (pin "2") (pinfunction "TAP_2") (pintype "passive"))
      (node (ref "R17") (pin "2") (pinfunction "2_2") (pintype "passive"))
      (node (ref "R9") (pin "2") (pinfunction "2_2") (pintype "passive"))
      (node (ref "TP12") (pin "1") (pinfunction "1_1") (pintype "passive"))
      (node (ref "X1") (pin "1") (pinfunction "Vcc_1") (pintype "passive"))
    )
    (net (code "64") (name "unconnected-(K4A-1~{Q}-Pad6)") (class "Default")
      (node (ref "K4") (pin "6") (pinfunction "1~{Q}_6") (pintype "passive+no_connect"))
    )
    (net (code "65") (name "unconnected-(K4A-1~{S}-Pad4)") (class "Default")
      (node (ref "K4") (pin "4") (pinfunction "1~{S}_4") (pintype "passive+no_connect"))
    )
    (net (code "66") (name "unconnected-(K4B-2~{Q}-Pad8)") (class "Default")
      (node (ref "K4") (pin "8") (pinfunction "2~{Q}_8") (pintype "passive+no_connect"))
    )
    (net (code "67") (name "unconnected-(K4B-2~{S}-Pad10)") (class "Default")
      (node (ref "K4") (pin "10") (pinfunction "2~{S}_10") (pintype "passive+no_connect"))
    )
    (net (code "68") (name "unconnected-(K6-NC-Pad1)") (class "Default")
      (node (ref "K6") (pin "1") (pinfunction "NC_1") (pintype "passive+no_connect"))
    )
    (net (code "69") (name "unconnected-(K7-NC-Pad1)") (class "Default")
      (node (ref "K7") (pin "1") (pinfunction "NC_1") (pintype "passive+no_connect"))
    )
    (net (code "70") (name "unconnected-(K8-NC-Pad1)") (class "Default")
      (node (ref "K8") (pin "1") (pinfunction "NC_1") (pintype "passive+no_connect"))
    )
    (net (code "71") (name "unconnected-(K12-NC-Pad5)") (class "Default")
      (node (ref "K12") (pin "5") (pinfunction "NC_5") (pintype "passive+no_connect"))
    )
    (net (code "72") (name "unconnected-(R3-TOP-Pad3)") (class "Default")
      (node (ref "R3") (pin "3") (pinfunction "TOP_3") (pintype "passive+no_connect"))
    )
    (net (code "73") (name "unconnected-(R6-TOP-Pad3)") (class "Default")
      (node (ref "R6") (pin "3") (pinfunction "TOP_3") (pintype "passive+no_connect"))
    )
    (net (code "74") (name "unconnected-(R12-TOP-Pad3)") (class "Default")
      (node (ref "R12") (pin "3") (pinfunction "TOP_3") (pintype "passive+no_connect"))
    )
  )
)
